# Line_Tracer_SET.net
KiCad netlist of a schematic drawn in EAGLE
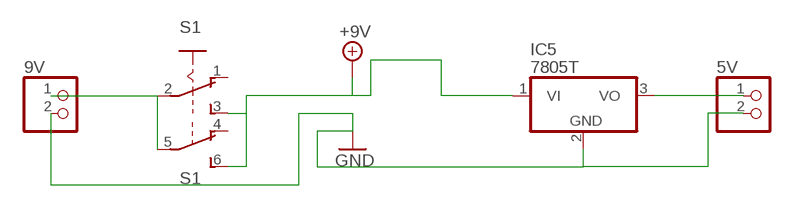
[diagram p0: schematic, sheet 1, part 1 of 2]
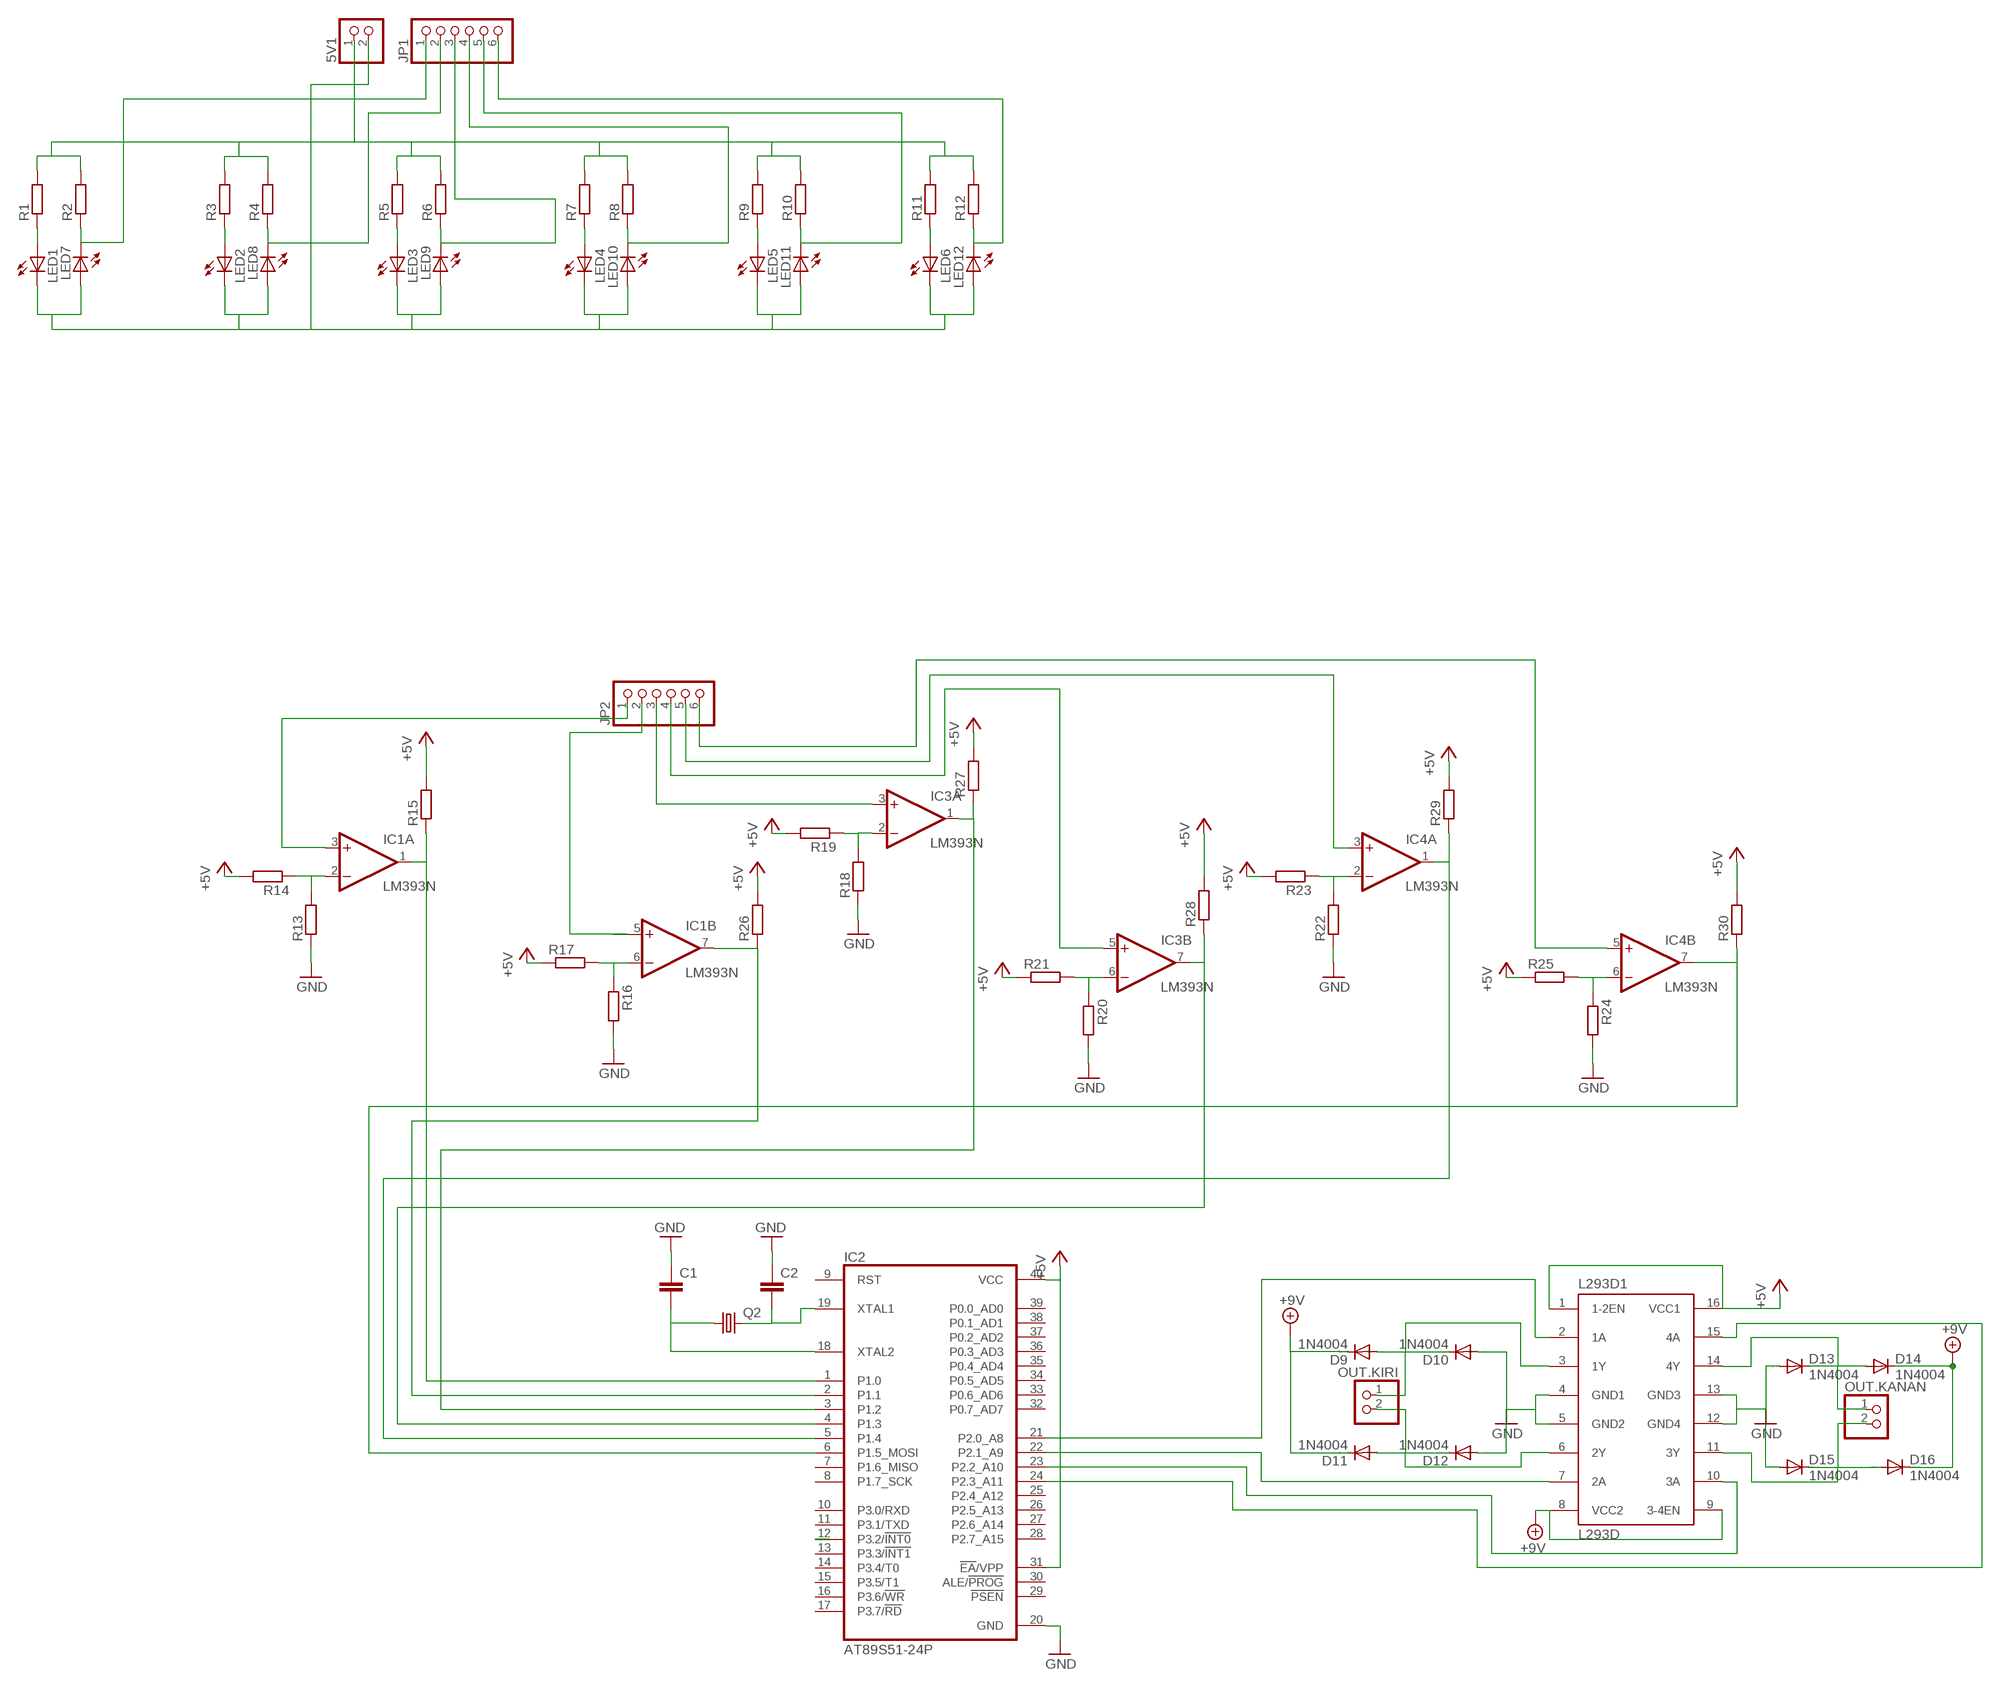
[diagram p1: schematic, sheet 1, part 2 of 2]

(export (version "E")
  (design (tool "Eeschema 10.0.6"))
  (components
    (comp (ref "5V")
      (value "PINHD-1X2")
      (footprint "eagle-import:1X02")
      (libsource (lib "eagle-import") (part "PINHD-1X2"))
    )
    (comp (ref "5V1")
      (value "PINHD-1X2")
      (footprint "eagle-import:1X02")
      (libsource (lib "eagle-import") (part "PINHD-1X2"))
    )
    (comp (ref "9V")
      (value "PINHD-1X2")
      (footprint "eagle-import:1X02")
      (libsource (lib "eagle-import") (part "PINHD-1X2"))
    )
    (comp (ref "C1")
      (value "C-EU025-024X044")
      (footprint "eagle-import:C025-024X044")
      (libsource (lib "eagle-import") (part "C-EU025-024X044"))
    )
    (comp (ref "C2")
      (value "C-EU025-024X044")
      (footprint "eagle-import:C025-024X044")
      (libsource (lib "eagle-import") (part "C-EU025-024X044"))
    )
    (comp (ref "D9")
      (value "1N4004")
      (footprint "eagle-import:DO41-10")
      (libsource (lib "eagle-import") (part "1N4004"))
    )
    (comp (ref "D10")
      (value "1N4004")
      (footprint "eagle-import:DO41-10")
      (libsource (lib "eagle-import") (part "1N4004"))
    )
    (comp (ref "D11")
      (value "1N4004")
      (footprint "eagle-import:DO41-10")
      (libsource (lib "eagle-import") (part "1N4004"))
    )
    (comp (ref "D12")
      (value "1N4004")
      (footprint "eagle-import:DO41-10")
      (libsource (lib "eagle-import") (part "1N4004"))
    )
    (comp (ref "D13")
      (value "1N4004")
      (footprint "eagle-import:DO41-10")
      (libsource (lib "eagle-import") (part "1N4004"))
    )
    (comp (ref "D14")
      (value "1N4004")
      (footprint "eagle-import:DO41-10")
      (libsource (lib "eagle-import") (part "1N4004"))
    )
    (comp (ref "D15")
      (value "1N4004")
      (footprint "eagle-import:DO41-10")
      (libsource (lib "eagle-import") (part "1N4004"))
    )
    (comp (ref "D16")
      (value "1N4004")
      (footprint "eagle-import:DO41-10")
      (libsource (lib "eagle-import") (part "1N4004"))
    )
    (comp (ref "IC1")
      (value "LM393N")
      (footprint "eagle-import:DIL08")
      (libsource (lib "eagle-import") (part "LM393N"))
    )
    (comp (ref "IC2")
      (value "AT89S51-24P")
      (footprint "eagle-import:DIL40")
      (fields (field (name "MPN") "AT89S51-24PU"))
      (libsource (lib "eagle-import") (part "AT89S51-P24"))
    )
    (comp (ref "IC3")
      (value "LM393N")
      (footprint "eagle-import:DIL08")
      (libsource (lib "eagle-import") (part "LM393N"))
    )
    (comp (ref "IC4")
      (value "LM393N")
      (footprint "eagle-import:DIL08")
      (libsource (lib "eagle-import") (part "LM393N"))
    )
    (comp (ref "IC5")
      (value "7805T")
      (footprint "eagle-import:TO220H")
      (libsource (lib "eagle-import") (part "78T05"))
    )
    (comp (ref "JP1")
      (value "PINHD-1X6")
      (footprint "eagle-import:1X06")
      (libsource (lib "eagle-import") (part "PINHD-1X6"))
    )
    (comp (ref "JP2")
      (value "PINHD-1X6")
      (footprint "eagle-import:1X06")
      (libsource (lib "eagle-import") (part "PINHD-1X6"))
    )
    (comp (ref "L293D1")
      (value "L293D")
      (footprint "eagle-import:DIL16")
      (libsource (lib "eagle-import") (part "L293D"))
    )
    (comp (ref "LED1")
      (value "LED3MM")
      (footprint "eagle-import:LED3MM")
      (libsource (lib "eagle-import") (part "LED3MM"))
    )
    (comp (ref "LED2")
      (value "LED3MM")
      (footprint "eagle-import:LED3MM")
      (libsource (lib "eagle-import") (part "LED3MM"))
    )
    (comp (ref "LED3")
      (value "LED3MM")
      (footprint "eagle-import:LED3MM")
      (libsource (lib "eagle-import") (part "LED3MM"))
    )
    (comp (ref "LED4")
      (value "LED3MM")
      (footprint "eagle-import:LED3MM")
      (libsource (lib "eagle-import") (part "LED3MM"))
    )
    (comp (ref "LED5")
      (value "LED3MM")
      (footprint "eagle-import:LED3MM")
      (libsource (lib "eagle-import") (part "LED3MM"))
    )
    (comp (ref "LED6")
      (value "LED3MM")
      (footprint "eagle-import:LED3MM")
      (libsource (lib "eagle-import") (part "LED3MM"))
    )
    (comp (ref "LED7")
      (value "LED3MM")
      (footprint "eagle-import:LED3MM")
      (libsource (lib "eagle-import") (part "LED3MM"))
    )
    (comp (ref "LED8")
      (value "LED3MM")
      (footprint "eagle-import:LED3MM")
      (libsource (lib "eagle-import") (part "LED3MM"))
    )
    (comp (ref "LED9")
      (value "LED3MM")
      (footprint "eagle-import:LED3MM")
      (libsource (lib "eagle-import") (part "LED3MM"))
    )
    (comp (ref "LED10")
      (value "LED3MM")
      (footprint "eagle-import:LED3MM")
      (libsource (lib "eagle-import") (part "LED3MM"))
    )
    (comp (ref "LED11")
      (value "LED3MM")
      (footprint "eagle-import:LED3MM")
      (libsource (lib "eagle-import") (part "LED3MM"))
    )
    (comp (ref "LED12")
      (value "LED3MM")
      (footprint "eagle-import:LED3MM")
      (libsource (lib "eagle-import") (part "LED3MM"))
    )
    (comp (ref "OUT.KANAN")
      (value "PINHD-1X2")
      (footprint "eagle-import:1X02")
      (libsource (lib "eagle-import") (part "PINHD-1X2"))
    )
    (comp (ref "OUT.KIRI")
      (value "PINHD-1X2")
      (footprint "eagle-import:1X02")
      (libsource (lib "eagle-import") (part "PINHD-1X2"))
    )
    (comp (ref "Q2")
      (value "CRYSTALHC49S")
      (footprint "eagle-import:HC49_S")
      (libsource (lib "eagle-import") (part "CRYSTALHC49S"))
    )
    (comp (ref "R1")
      (value "R-EU_0207/10")
      (footprint "eagle-import:0207_10")
      (libsource (lib "eagle-import") (part "R-EU_0207/10"))
    )
    (comp (ref "R2")
      (value "R-EU_0207/10")
      (footprint "eagle-import:0207_10")
      (libsource (lib "eagle-import") (part "R-EU_0207/10"))
    )
    (comp (ref "R3")
      (value "R-EU_0207/10")
      (footprint "eagle-import:0207_10")
      (libsource (lib "eagle-import") (part "R-EU_0207/10"))
    )
    (comp (ref "R4")
      (value "R-EU_0207/10")
      (footprint "eagle-import:0207_10")
      (libsource (lib "eagle-import") (part "R-EU_0207/10"))
    )
    (comp (ref "R5")
      (value "R-EU_0207/10")
      (footprint "eagle-import:0207_10")
      (libsource (lib "eagle-import") (part "R-EU_0207/10"))
    )
    (comp (ref "R6")
      (value "R-EU_0207/10")
      (footprint "eagle-import:0207_10")
      (libsource (lib "eagle-import") (part "R-EU_0207/10"))
    )
    (comp (ref "R7")
      (value "R-EU_0207/10")
      (footprint "eagle-import:0207_10")
      (libsource (lib "eagle-import") (part "R-EU_0207/10"))
    )
    (comp (ref "R8")
      (value "R-EU_0207/10")
      (footprint "eagle-import:0207_10")
      (libsource (lib "eagle-import") (part "R-EU_0207/10"))
    )
    (comp (ref "R9")
      (value "R-EU_0207/10")
      (footprint "eagle-import:0207_10")
      (libsource (lib "eagle-import") (part "R-EU_0207/10"))
    )
    (comp (ref "R10")
      (value "R-EU_0207/10")
      (footprint "eagle-import:0207_10")
      (libsource (lib "eagle-import") (part "R-EU_0207/10"))
    )
    (comp (ref "R11")
      (value "R-EU_0207/10")
      (footprint "eagle-import:0207_10")
      (libsource (lib "eagle-import") (part "R-EU_0207/10"))
    )
    (comp (ref "R12")
      (value "R-EU_0207/10")
      (footprint "eagle-import:0207_10")
      (libsource (lib "eagle-import") (part "R-EU_0207/10"))
    )
    (comp (ref "R13")
      (value "R-EU_0207/10")
      (footprint "eagle-import:0207_10")
      (libsource (lib "eagle-import") (part "R-EU_0207/10"))
    )
    (comp (ref "R14")
      (value "R-EU_0207/10")
      (footprint "eagle-import:0207_10")
      (libsource (lib "eagle-import") (part "R-EU_0207/10"))
    )
    (comp (ref "R15")
      (value "R-EU_0207/10")
      (footprint "eagle-import:0207_10")
      (libsource (lib "eagle-import") (part "R-EU_0207/10"))
    )
    (comp (ref "R16")
      (value "R-EU_0207/10")
      (footprint "eagle-import:0207_10")
      (libsource (lib "eagle-import") (part "R-EU_0207/10"))
    )
    (comp (ref "R17")
      (value "R-EU_0207/10")
      (footprint "eagle-import:0207_10")
      (libsource (lib "eagle-import") (part "R-EU_0207/10"))
    )
    (comp (ref "R18")
      (value "R-EU_0207/10")
      (footprint "eagle-import:0207_10")
      (libsource (lib "eagle-import") (part "R-EU_0207/10"))
    )
    (comp (ref "R19")
      (value "R-EU_0207/10")
      (footprint "eagle-import:0207_10")
      (libsource (lib "eagle-import") (part "R-EU_0207/10"))
    )
    (comp (ref "R20")
      (value "R-EU_0207/10")
      (footprint "eagle-import:0207_10")
      (libsource (lib "eagle-import") (part "R-EU_0207/10"))
    )
    (comp (ref "R21")
      (value "R-EU_0207/10")
      (footprint "eagle-import:0207_10")
      (libsource (lib "eagle-import") (part "R-EU_0207/10"))
    )
    (comp (ref "R22")
      (value "R-EU_0207/10")
      (footprint "eagle-import:0207_10")
      (libsource (lib "eagle-import") (part "R-EU_0207/10"))
    )
    (comp (ref "R23")
      (value "R-EU_0207/10")
      (footprint "eagle-import:0207_10")
      (libsource (lib "eagle-import") (part "R-EU_0207/10"))
    )
    (comp (ref "R24")
      (value "R-EU_0207/10")
      (footprint "eagle-import:0207_10")
      (libsource (lib "eagle-import") (part "R-EU_0207/10"))
    )
    (comp (ref "R25")
      (value "R-EU_0207/10")
      (footprint "eagle-import:0207_10")
      (libsource (lib "eagle-import") (part "R-EU_0207/10"))
    )
    (comp (ref "R26")
      (value "R-EU_0207/10")
      (footprint "eagle-import:0207_10")
      (libsource (lib "eagle-import") (part "R-EU_0207/10"))
    )
    (comp (ref "R27")
      (value "R-EU_0207/10")
      (footprint "eagle-import:0207_10")
      (libsource (lib "eagle-import") (part "R-EU_0207/10"))
    )
    (comp (ref "R28")
      (value "R-EU_0207/10")
      (footprint "eagle-import:0207_10")
      (libsource (lib "eagle-import") (part "R-EU_0207/10"))
    )
    (comp (ref "R29")
      (value "R-EU_0207/10")
      (footprint "eagle-import:0207_10")
      (libsource (lib "eagle-import") (part "R-EU_0207/10"))
    )
    (comp (ref "R30")
      (value "R-EU_0207/10")
      (footprint "eagle-import:0207_10")
      (libsource (lib "eagle-import") (part "R-EU_0207/10"))
    )
    (comp (ref "S1")
      (value "A68-A31")
      (footprint "eagle-import:A68-A31")
      (libsource (lib "eagle-import") (part "A68-A31"))
    )
  )
  (nets
    (net (code "1") (name "+5V") (class "Default")
      (node (ref "IC2") (pin "31") (pinfunction "~{EA}/VPP_31") (pintype "input"))
      (node (ref "IC2") (pin "40") (pinfunction "VCC_40") (pintype "power_in"))
      (node (ref "L293D1") (pin "1") (pinfunction "1-2EN_1") (pintype "input"))
      (node (ref "L293D1") (pin "16") (pinfunction "VCC1_16") (pintype "power_in"))
      (node (ref "R14") (pin "2") (pinfunction "2_2") (pintype "passive"))
      (node (ref "R15") (pin "2") (pinfunction "2_2") (pintype "passive"))
      (node (ref "R17") (pin "1") (pinfunction "1_1") (pintype "passive"))
      (node (ref "R19") (pin "2") (pinfunction "2_2") (pintype "passive"))
      (node (ref "R21") (pin "1") (pinfunction "1_1") (pintype "passive"))
      (node (ref "R23") (pin "2") (pinfunction "2_2") (pintype "passive"))
      (node (ref "R25") (pin "1") (pinfunction "1_1") (pintype "passive"))
      (node (ref "R26") (pin "2") (pinfunction "2_2") (pintype "passive"))
      (node (ref "R27") (pin "2") (pinfunction "2_2") (pintype "passive"))
      (node (ref "R28") (pin "2") (pinfunction "2_2") (pintype "passive"))
      (node (ref "R29") (pin "2") (pinfunction "2_2") (pintype "passive"))
      (node (ref "R30") (pin "2") (pinfunction "2_2") (pintype "passive"))
    )
    (net (code "2") (name "+9V") (class "Default")
      (node (ref "D11") (pin "C") (pinfunction "C_C") (pintype "passive"))
      (node (ref "D14") (pin "C") (pinfunction "C_C") (pintype "passive"))
      (node (ref "D16") (pin "C") (pinfunction "C_C") (pintype "passive"))
      (node (ref "D9") (pin "C") (pinfunction "C_C") (pintype "passive"))
      (node (ref "IC5") (pin "1") (pinfunction "VI_1") (pintype "input"))
      (node (ref "L293D1") (pin "8") (pinfunction "VCC2_8") (pintype "power_in"))
      (node (ref "L293D1") (pin "9") (pinfunction "3-4EN_9") (pintype "input"))
      (node (ref "S1") (pin "3") (pinfunction "S_3") (pintype "passive"))
      (node (ref "S1") (pin "6") (pinfunction "S_6") (pintype "passive"))
    )
    (net (code "3") (name "GND") (class "Default")
      (node (ref "5V") (pin "2") (pinfunction "2_2") (pintype "passive"))
      (node (ref "9V") (pin "2") (pinfunction "2_2") (pintype "passive"))
      (node (ref "C1") (pin "1") (pinfunction "1_1") (pintype "passive"))
      (node (ref "C2") (pin "1") (pinfunction "1_1") (pintype "passive"))
      (node (ref "D10") (pin "A") (pinfunction "A_A") (pintype "passive"))
      (node (ref "D12") (pin "A") (pinfunction "A_A") (pintype "passive"))
      (node (ref "D13") (pin "A") (pinfunction "A_A") (pintype "passive"))
      (node (ref "D15") (pin "A") (pinfunction "A_A") (pintype "passive"))
      (node (ref "IC2") (pin "20") (pinfunction "GND_20") (pintype "power_in"))
      (node (ref "IC5") (pin "2") (pinfunction "GND_2") (pintype "passive"))
      (node (ref "L293D1") (pin "12") (pinfunction "GND4_12") (pintype "power_in"))
      (node (ref "L293D1") (pin "13") (pinfunction "GND3_13") (pintype "power_in"))
      (node (ref "L293D1") (pin "4") (pinfunction "GND1_4") (pintype "power_in"))
      (node (ref "L293D1") (pin "5") (pinfunction "GND2_5") (pintype "power_in"))
      (node (ref "R13") (pin "1") (pinfunction "1_1") (pintype "passive"))
      (node (ref "R16") (pin "2") (pinfunction "2_2") (pintype "passive"))
      (node (ref "R18") (pin "1") (pinfunction "1_1") (pintype "passive"))
      (node (ref "R20") (pin "2") (pinfunction "2_2") (pintype "passive"))
      (node (ref "R22") (pin "1") (pinfunction "1_1") (pintype "passive"))
      (node (ref "R24") (pin "2") (pinfunction "2_2") (pintype "passive"))
    )
    (net (code "4") (name "Net-(5V1-Pad1)") (class "Default")
      (node (ref "5V1") (pin "1") (pinfunction "1_1") (pintype "passive"))
      (node (ref "R1") (pin "2") (pinfunction "2_2") (pintype "passive"))
      (node (ref "R10") (pin "2") (pinfunction "2_2") (pintype "passive"))
      (node (ref "R11") (pin "2") (pinfunction "2_2") (pintype "passive"))
      (node (ref "R12") (pin "2") (pinfunction "2_2") (pintype "passive"))
      (node (ref "R2") (pin "2") (pinfunction "2_2") (pintype "passive"))
      (node (ref "R3") (pin "2") (pinfunction "2_2") (pintype "passive"))
      (node (ref "R4") (pin "2") (pinfunction "2_2") (pintype "passive"))
      (node (ref "R5") (pin "2") (pinfunction "2_2") (pintype "passive"))
      (node (ref "R6") (pin "2") (pinfunction "2_2") (pintype "passive"))
      (node (ref "R7") (pin "2") (pinfunction "2_2") (pintype "passive"))
      (node (ref "R8") (pin "2") (pinfunction "2_2") (pintype "passive"))
      (node (ref "R9") (pin "2") (pinfunction "2_2") (pintype "passive"))
    )
    (net (code "5") (name "Net-(IC1A-+IN)") (class "Default")
      (node (ref "IC1") (pin "3") (pinfunction "+IN_3") (pintype "input"))
      (node (ref "JP2") (pin "1") (pinfunction "1_1") (pintype "passive"))
    )
    (net (code "6") (name "Net-(IC1A--IN)") (class "Default")
      (node (ref "IC1") (pin "2") (pinfunction "-IN_2") (pintype "input"))
      (node (ref "R13") (pin "2") (pinfunction "2_2") (pintype "passive"))
      (node (ref "R14") (pin "1") (pinfunction "1_1") (pintype "passive"))
    )
    (net (code "7") (name "Net-(IC1A-OUT)") (class "Default")
      (node (ref "IC1") (pin "1") (pinfunction "OUT_1") (pintype "output"))
      (node (ref "IC2") (pin "1") (pinfunction "P1.0_1") (pintype "bidirectional"))
      (node (ref "R15") (pin "1") (pinfunction "1_1") (pintype "passive"))
    )
    (net (code "8") (name "Net-(IC1B-+IN)") (class "Default")
      (node (ref "IC1") (pin "5") (pinfunction "+IN_5") (pintype "input"))
      (node (ref "JP2") (pin "2") (pinfunction "2_2") (pintype "passive"))
    )
    (net (code "9") (name "Net-(IC1B--IN)") (class "Default")
      (node (ref "IC1") (pin "6") (pinfunction "-IN_6") (pintype "input"))
      (node (ref "R16") (pin "1") (pinfunction "1_1") (pintype "passive"))
      (node (ref "R17") (pin "2") (pinfunction "2_2") (pintype "passive"))
    )
    (net (code "10") (name "Net-(IC1B-OUT)") (class "Default")
      (node (ref "IC1") (pin "7") (pinfunction "OUT_7") (pintype "output"))
      (node (ref "IC2") (pin "2") (pinfunction "P1.1_2") (pintype "bidirectional"))
      (node (ref "R26") (pin "1") (pinfunction "1_1") (pintype "passive"))
    )
    (net (code "11") (name "Net-(IC2-P1.2)") (class "Default")
      (node (ref "IC2") (pin "3") (pinfunction "P1.2_3") (pintype "bidirectional"))
      (node (ref "IC3") (pin "1") (pinfunction "OUT_1") (pintype "output"))
      (node (ref "R27") (pin "1") (pinfunction "1_1") (pintype "passive"))
    )
    (net (code "12") (name "Net-(IC2-P1.3)") (class "Default")
      (node (ref "IC2") (pin "4") (pinfunction "P1.3_4") (pintype "bidirectional"))
      (node (ref "IC3") (pin "7") (pinfunction "OUT_7") (pintype "output"))
      (node (ref "R28") (pin "1") (pinfunction "1_1") (pintype "passive"))
    )
    (net (code "13") (name "Net-(IC2-P1.4)") (class "Default")
      (node (ref "IC2") (pin "5") (pinfunction "P1.4_5") (pintype "bidirectional"))
      (node (ref "IC4") (pin "1") (pinfunction "OUT_1") (pintype "output"))
      (node (ref "R29") (pin "1") (pinfunction "1_1") (pintype "passive"))
    )
    (net (code "14") (name "Net-(IC2-P1.5_MOSI)") (class "Default")
      (node (ref "IC2") (pin "6") (pinfunction "P1.5_MOSI_6") (pintype "bidirectional"))
      (node (ref "IC4") (pin "7") (pinfunction "OUT_7") (pintype "output"))
      (node (ref "R30") (pin "1") (pinfunction "1_1") (pintype "passive"))
    )
    (net (code "15") (name "Net-(IC2-P2.0_A8)") (class "Default")
      (node (ref "IC2") (pin "21") (pinfunction "P2.0_A8_21") (pintype "bidirectional"))
      (node (ref "L293D1") (pin "2") (pinfunction "1A_2") (pintype "input"))
    )
    (net (code "16") (name "Net-(IC2-P2.1_A9)") (class "Default")
      (node (ref "IC2") (pin "22") (pinfunction "P2.1_A9_22") (pintype "bidirectional"))
      (node (ref "L293D1") (pin "7") (pinfunction "2A_7") (pintype "input"))
    )
    (net (code "17") (name "Net-(IC2-P2.2_A10)") (class "Default")
      (node (ref "IC2") (pin "23") (pinfunction "P2.2_A10_23") (pintype "bidirectional"))
      (node (ref "L293D1") (pin "10") (pinfunction "3A_10") (pintype "input"))
    )
    (net (code "18") (name "Net-(IC2-P2.3_A11)") (class "Default")
      (node (ref "IC2") (pin "24") (pinfunction "P2.3_A11_24") (pintype "bidirectional"))
      (node (ref "L293D1") (pin "15") (pinfunction "4A_15") (pintype "input"))
    )
    (net (code "19") (name "Net-(IC2-XTAL1)") (class "Default")
      (node (ref "C2") (pin "2") (pinfunction "2_2") (pintype "passive"))
      (node (ref "IC2") (pin "19") (pinfunction "XTAL1_19") (pintype "input"))
      (node (ref "Q2") (pin "2") (pinfunction "2_2") (pintype "passive"))
    )
    (net (code "20") (name "Net-(IC2-XTAL2)") (class "Default")
      (node (ref "C1") (pin "2") (pinfunction "2_2") (pintype "passive"))
      (node (ref "IC2") (pin "18") (pinfunction "XTAL2_18") (pintype "input"))
      (node (ref "Q2") (pin "1") (pinfunction "1_1") (pintype "passive"))
    )
    (net (code "21") (name "Net-(IC3A-+IN)") (class "Default")
      (node (ref "IC3") (pin "3") (pinfunction "+IN_3") (pintype "input"))
      (node (ref "JP2") (pin "3") (pinfunction "3_3") (pintype "passive"))
    )
    (net (code "22") (name "Net-(IC3A--IN)") (class "Default")
      (node (ref "IC3") (pin "2") (pinfunction "-IN_2") (pintype "input"))
      (node (ref "R18") (pin "2") (pinfunction "2_2") (pintype "passive"))
      (node (ref "R19") (pin "1") (pinfunction "1_1") (pintype "passive"))
    )
    (net (code "23") (name "Net-(IC3B-+IN)") (class "Default")
      (node (ref "IC3") (pin "5") (pinfunction "+IN_5") (pintype "input"))
      (node (ref "JP2") (pin "4") (pinfunction "4_4") (pintype "passive"))
    )
    (net (code "24") (name "Net-(IC3B--IN)") (class "Default")
      (node (ref "IC3") (pin "6") (pinfunction "-IN_6") (pintype "input"))
      (node (ref "R20") (pin "1") (pinfunction "1_1") (pintype "passive"))
      (node (ref "R21") (pin "2") (pinfunction "2_2") (pintype "passive"))
    )
    (net (code "25") (name "Net-(IC4A-+IN)") (class "Default")
      (node (ref "IC4") (pin "3") (pinfunction "+IN_3") (pintype "input"))
      (node (ref "JP2") (pin "5") (pinfunction "5_5") (pintype "passive"))
    )
    (net (code "26") (name "Net-(IC4A--IN)") (class "Default")
      (node (ref "IC4") (pin "2") (pinfunction "-IN_2") (pintype "input"))
      (node (ref "R22") (pin "2") (pinfunction "2_2") (pintype "passive"))
      (node (ref "R23") (pin "1") (pinfunction "1_1") (pintype "passive"))
    )
    (net (code "27") (name "Net-(IC4B-+IN)") (class "Default")
      (node (ref "IC4") (pin "5") (pinfunction "+IN_5") (pintype "input"))
      (node (ref "JP2") (pin "6") (pinfunction "6_6") (pintype "passive"))
    )
    (net (code "28") (name "Net-(IC4B--IN)") (class "Default")
      (node (ref "IC4") (pin "6") (pinfunction "-IN_6") (pintype "input"))
      (node (ref "R24") (pin "1") (pinfunction "1_1") (pintype "passive"))
      (node (ref "R25") (pin "2") (pinfunction "2_2") (pintype "passive"))
    )
    (net (code "29") (name "Net-(IC5-VO)") (class "Default")
      (node (ref "5V") (pin "1") (pinfunction "1_1") (pintype "passive"))
      (node (ref "IC5") (pin "3") (pinfunction "VO_3") (pintype "passive"))
    )
    (net (code "30") (name "Net-(L293D1-1Y)") (class "Default")
      (node (ref "D10") (pin "C") (pinfunction "C_C") (pintype "passive"))
      (node (ref "D9") (pin "A") (pinfunction "A_A") (pintype "passive"))
      (node (ref "L293D1") (pin "3") (pinfunction "1Y_3") (pintype "output"))
      (node (ref "OUT.KIRI") (pin "1") (pinfunction "1_1") (pintype "passive"))
    )
    (net (code "31") (name "Net-(L293D1-2Y)") (class "Default")
      (node (ref "D11") (pin "A") (pinfunction "A_A") (pintype "passive"))
      (node (ref "D12") (pin "C") (pinfunction "C_C") (pintype "passive"))
      (node (ref "L293D1") (pin "6") (pinfunction "2Y_6") (pintype "output"))
      (node (ref "OUT.KIRI") (pin "2") (pinfunction "2_2") (pintype "passive"))
    )
    (net (code "32") (name "Net-(L293D1-3Y)") (class "Default")
      (node (ref "D15") (pin "C") (pinfunction "C_C") (pintype "passive"))
      (node (ref "D16") (pin "A") (pinfunction "A_A") (pintype "passive"))
      (node (ref "L293D1") (pin "11") (pinfunction "3Y_11") (pintype "output"))
      (node (ref "OUT.KANAN") (pin "2") (pinfunction "2_2") (pintype "passive"))
    )
    (net (code "33") (name "Net-(L293D1-4Y)") (class "Default")
      (node (ref "D13") (pin "C") (pinfunction "C_C") (pintype "passive"))
      (node (ref "D14") (pin "A") (pinfunction "A_A") (pintype "passive"))
      (node (ref "L293D1") (pin "14") (pinfunction "4Y_14") (pintype "output"))
      (node (ref "OUT.KANAN") (pin "1") (pinfunction "1_1") (pintype "passive"))
    )
    (net (code "34") (name "Net-(LED1-C)") (class "Default")
      (node (ref "5V1") (pin "2") (pinfunction "2_2") (pintype "passive"))
      (node (ref "LED1") (pin "K") (pinfunction "C_K") (pintype "passive"))
      (node (ref "LED10") (pin "A") (pinfunction "A_A") (pintype "passive"))
      (node (ref "LED11") (pin "A") (pinfunction "A_A") (pintype "passive"))
      (node (ref "LED12") (pin "A") (pinfunction "A_A") (pintype "passive"))
      (node (ref "LED2") (pin "K") (pinfunction "C_K") (pintype "passive"))
      (node (ref "LED3") (pin "K") (pinfunction "C_K") (pintype "passive"))
      (node (ref "LED4") (pin "K") (pinfunction "C_K") (pintype "passive"))
      (node (ref "LED5") (pin "K") (pinfunction "C_K") (pintype "passive"))
      (node (ref "LED6") (pin "K") (pinfunction "C_K") (pintype "passive"))
      (node (ref "LED7") (pin "A") (pinfunction "A_A") (pintype "passive"))
      (node (ref "LED8") (pin "A") (pinfunction "A_A") (pintype "passive"))
      (node (ref "LED9") (pin "A") (pinfunction "A_A") (pintype "passive"))
    )
    (net (code "35") (name "Net-(LED1-PadA)") (class "Default")
      (node (ref "LED1") (pin "A") (pinfunction "A_A") (pintype "passive"))
      (node (ref "R1") (pin "1") (pinfunction "1_1") (pintype "passive"))
    )
    (net (code "36") (name "Net-(LED2-PadA)") (class "Default")
      (node (ref "LED2") (pin "A") (pinfunction "A_A") (pintype "passive"))
      (node (ref "R3") (pin "1") (pinfunction "1_1") (pintype "passive"))
    )
    (net (code "37") (name "Net-(LED3-PadA)") (class "Default")
      (node (ref "LED3") (pin "A") (pinfunction "A_A") (pintype "passive"))
      (node (ref "R5") (pin "1") (pinfunction "1_1") (pintype "passive"))
    )
    (net (code "38") (name "Net-(LED4-PadA)") (class "Default")
      (node (ref "LED4") (pin "A") (pinfunction "A_A") (pintype "passive"))
      (node (ref "R7") (pin "1") (pinfunction "1_1") (pintype "passive"))
    )
    (net (code "39") (name "Net-(LED5-PadA)") (class "Default")
      (node (ref "LED5") (pin "A") (pinfunction "A_A") (pintype "passive"))
      (node (ref "R9") (pin "1") (pinfunction "1_1") (pintype "passive"))
    )
    (net (code "40") (name "Net-(LED6-PadA)") (class "Default")
      (node (ref "LED6") (pin "A") (pinfunction "A_A") (pintype "passive"))
      (node (ref "R11") (pin "1") (pinfunction "1_1") (pintype "passive"))
    )
    (net (code "41") (name "Net-(LED7-C)") (class "Default")
      (node (ref "JP1") (pin "1") (pinfunction "1_1") (pintype "passive"))
      (node (ref "LED7") (pin "K") (pinfunction "C_K") (pintype "passive"))
      (node (ref "R2") (pin "1") (pinfunction "1_1") (pintype "passive"))
    )
    (net (code "42") (name "Net-(LED8-C)") (class "Default")
      (node (ref "JP1") (pin "2") (pinfunction "2_2") (pintype "passive"))
      (node (ref "LED8") (pin "K") (pinfunction "C_K") (pintype "passive"))
      (node (ref "R4") (pin "1") (pinfunction "1_1") (pintype "passive"))
    )
    (net (code "43") (name "Net-(LED9-C)") (class "Default")
      (node (ref "JP1") (pin "3") (pinfunction "3_3") (pintype "passive"))
      (node (ref "LED9") (pin "K") (pinfunction "C_K") (pintype "passive"))
      (node (ref "R6") (pin "1") (pinfunction "1_1") (pintype "passive"))
    )
    (net (code "44") (name "Net-(LED10-C)") (class "Default")
      (node (ref "JP1") (pin "4") (pinfunction "4_4") (pintype "passive"))
      (node (ref "LED10") (pin "K") (pinfunction "C_K") (pintype "passive"))
      (node (ref "R8") (pin "1") (pinfunction "1_1") (pintype "passive"))
    )
    (net (code "45") (name "Net-(LED11-C)") (class "Default")
      (node (ref "JP1") (pin "5") (pinfunction "5_5") (pintype "passive"))
      (node (ref "LED11") (pin "K") (pinfunction "C_K") (pintype "passive"))
      (node (ref "R10") (pin "1") (pinfunction "1_1") (pintype "passive"))
    )
    (net (code "46") (name "Net-(LED12-C)") (class "Default")
      (node (ref "JP1") (pin "6") (pinfunction "6_6") (pintype "passive"))
      (node (ref "LED12") (pin "K") (pinfunction "C_K") (pintype "passive"))
      (node (ref "R12") (pin "1") (pinfunction "1_1") (pintype "passive"))
    )
    (net (code "47") (name "Net-(S1A-P)") (class "Default")
      (node (ref "9V") (pin "1") (pinfunction "1_1") (pintype "passive"))
      (node (ref "S1") (pin "2") (pinfunction "P_2") (pintype "passive"))
      (node (ref "S1") (pin "5") (pinfunction "P_5") (pintype "passive"))
    )
    (net (code "48") (name "unconnected-(IC2-ALE{slash}~{PROG}-Pad30)") (class "Default")
      (node (ref "IC2") (pin "30") (pinfunction "ALE/~{PROG}_30") (pintype "output"))
    )
    (net (code "49") (name "unconnected-(IC2-P0.0_AD0-Pad39)") (class "Default")
      (node (ref "IC2") (pin "39") (pinfunction "P0.0_AD0_39") (pintype "bidirectional"))
    )
    (net (code "50") (name "unconnected-(IC2-P0.1_AD1-Pad38)") (class "Default")
      (node (ref "IC2") (pin "38") (pinfunction "P0.1_AD1_38") (pintype "bidirectional"))
    )
    (net (code "51") (name "unconnected-(IC2-P0.2_AD2-Pad37)") (class "Default")
      (node (ref "IC2") (pin "37") (pinfunction "P0.2_AD2_37") (pintype "bidirectional"))
    )
    (net (code "52") (name "unconnected-(IC2-P0.3_AD3-Pad36)") (class "Default")
      (node (ref "IC2") (pin "36") (pinfunction "P0.3_AD3_36") (pintype "bidirectional"))
    )
    (net (code "53") (name "unconnected-(IC2-P0.4_AD4-Pad35)") (class "Default")
      (node (ref "IC2") (pin "35") (pinfunction "P0.4_AD4_35") (pintype "bidirectional"))
    )
    (net (code "54") (name "unconnected-(IC2-P0.5_AD5-Pad34)") (class "Default")
      (node (ref "IC2") (pin "34") (pinfunction "P0.5_AD5_34") (pintype "bidirectional"))
    )
    (net (code "55") (name "unconnected-(IC2-P0.6_AD6-Pad33)") (class "Default")
      (node (ref "IC2") (pin "33") (pinfunction "P0.6_AD6_33") (pintype "bidirectional"))
    )
    (net (code "56") (name "unconnected-(IC2-P0.7_AD7-Pad32)") (class "Default")
      (node (ref "IC2") (pin "32") (pinfunction "P0.7_AD7_32") (pintype "bidirectional"))
    )
    (net (code "57") (name "unconnected-(IC2-P1.6_MISO-Pad7)") (class "Default")
      (node (ref "IC2") (pin "7") (pinfunction "P1.6_MISO_7") (pintype "bidirectional"))
    )
    (net (code "58") (name "unconnected-(IC2-P1.7_SCK-Pad8)") (class "Default")
      (node (ref "IC2") (pin "8") (pinfunction "P1.7_SCK_8") (pintype "bidirectional"))
    )
    (net (code "59") (name "unconnected-(IC2-P2.4_A12-Pad25)") (class "Default")
      (node (ref "IC2") (pin "25") (pinfunction "P2.4_A12_25") (pintype "bidirectional"))
    )
    (net (code "60") (name "unconnected-(IC2-P2.5_A13-Pad26)") (class "Default")
      (node (ref "IC2") (pin "26") (pinfunction "P2.5_A13_26") (pintype "bidirectional"))
    )
    (net (code "61") (name "unconnected-(IC2-P2.6_A14-Pad27)") (class "Default")
      (node (ref "IC2") (pin "27") (pinfunction "P2.6_A14_27") (pintype "bidirectional"))
    )
    (net (code "62") (name "unconnected-(IC2-P2.7_A15-Pad28)") (class "Default")
      (node (ref "IC2") (pin "28") (pinfunction "P2.7_A15_28") (pintype "bidirectional"))
    )
    (net (code "63") (name "unconnected-(IC2-P3.0{slash}RXD-Pad10)") (class "Default")
      (node (ref "IC2") (pin "10") (pinfunction "P3.0/RXD_10") (pintype "bidirectional"))
    )
    (net (code "64") (name "unconnected-(IC2-P3.1{slash}TXD-Pad11)") (class "Default")
      (node (ref "IC2") (pin "11") (pinfunction "P3.1/TXD_11") (pintype "bidirectional"))
    )
    (net (code "65") (name "unconnected-(IC2-P3.2{slash}~{INT0}-Pad12)") (class "Default")
      (node (ref "IC2") (pin "12") (pinfunction "P3.2/~{INT0}_12") (pintype "bidirectional"))
    )
    (net (code "66") (name "unconnected-(IC2-P3.3{slash}~{INT1}-Pad13)") (class "Default")
      (node (ref "IC2") (pin "13") (pinfunction "P3.3/~{INT1}_13") (pintype "bidirectional"))
    )
    (net (code "67") (name "unconnected-(IC2-P3.4{slash}T0-Pad14)") (class "Default")
      (node (ref "IC2") (pin "14") (pinfunction "P3.4/T0_14") (pintype "bidirectional"))
    )
    (net (code "68") (name "unconnected-(IC2-P3.5{slash}T1-Pad15)") (class "Default")
      (node (ref "IC2") (pin "15") (pinfunction "P3.5/T1_15") (pintype "bidirectional"))
    )
    (net (code "69") (name "unconnected-(IC2-P3.6{slash}~{WR}-Pad16)") (class "Default")
      (node (ref "IC2") (pin "16") (pinfunction "P3.6/~{WR}_16") (pintype "bidirectional"))
    )
    (net (code "70") (name "unconnected-(IC2-P3.7{slash}~{RD}-Pad17)") (class "Default")
      (node (ref "IC2") (pin "17") (pinfunction "P3.7/~{RD}_17") (pintype "bidirectional"))
    )
    (net (code "71") (name "unconnected-(IC2-RST-Pad9)") (class "Default")
      (node (ref "IC2") (pin "9") (pinfunction "RST_9") (pintype "input"))
    )
    (net (code "72") (name "unconnected-(IC2-~{PSEN}-Pad29)") (class "Default")
      (node (ref "IC2") (pin "29") (pinfunction "~{PSEN}_29") (pintype "output"))
    )
    (net (code "73") (name "unconnected-(S1A-O-Pad1)") (class "Default")
      (node (ref "S1") (pin "1") (pinfunction "O_1") (pintype "passive"))
    )
    (net (code "74") (name "unconnected-(S1B-O-Pad4)") (class "Default")
      (node (ref "S1") (pin "4") (pinfunction "O_4") (pintype "passive"))
    )
  )
)
